# TX.net
KiCad netlist of a schematic drawn in EAGLE
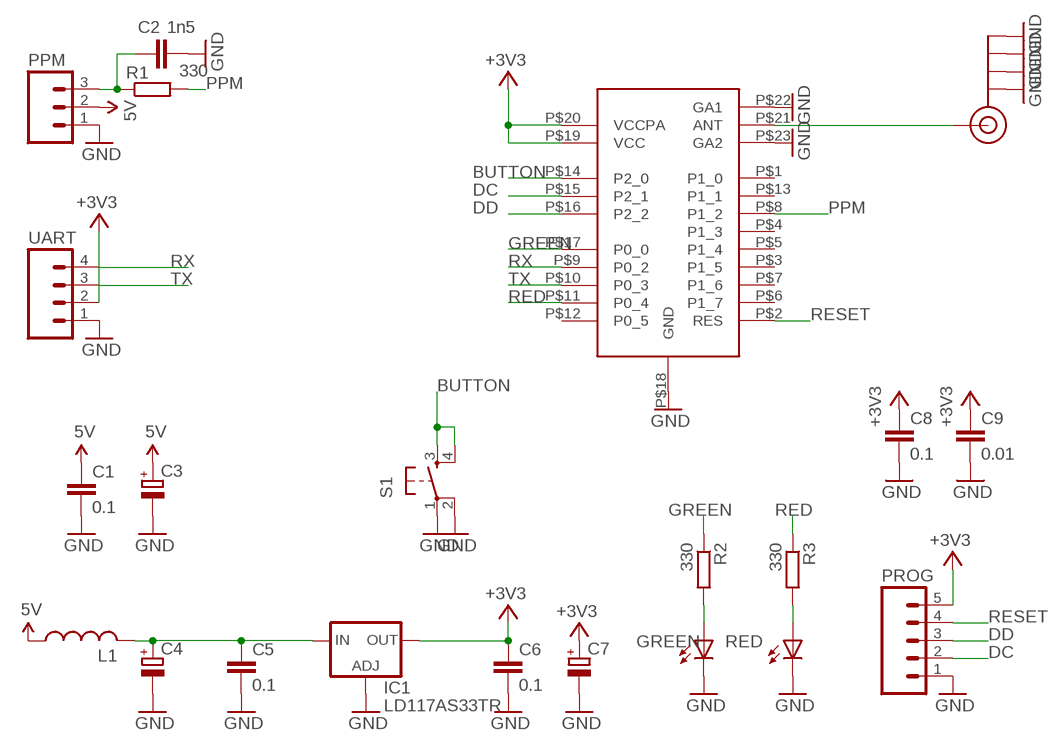
[diagram p0: schematic, sheet 1]

(export (version "E")
  (design (tool "Eeschema 10.0.6"))
  (components
    (comp (ref "C1")
      (value "0.1")
      (footprint "eagle-import:C0603")
      (libsource (lib "eagle-import") (part "C-EUC0603"))
    )
    (comp (ref "C2")
      (value "1n5")
      (footprint "eagle-import:C0603")
      (libsource (lib "eagle-import") (part "C-EUC0603"))
    )
    (comp (ref "C3")
      (value "CPOL-EUCT3216")
      (footprint "eagle-import:CT3216")
      (libsource (lib "eagle-import") (part "CPOL-EUCT3216"))
    )
    (comp (ref "C4")
      (value "CPOL-EUCT3216")
      (footprint "eagle-import:CT3216")
      (libsource (lib "eagle-import") (part "CPOL-EUCT3216"))
    )
    (comp (ref "C5")
      (value "0.1")
      (footprint "eagle-import:C0603")
      (libsource (lib "eagle-import") (part "C-EUC0603"))
    )
    (comp (ref "C6")
      (value "0.1")
      (footprint "eagle-import:C0603")
      (libsource (lib "eagle-import") (part "C-EUC0603"))
    )
    (comp (ref "C7")
      (value "CPOL-EUCT3216")
      (footprint "eagle-import:CT3216")
      (libsource (lib "eagle-import") (part "CPOL-EUCT3216"))
    )
    (comp (ref "C8")
      (value "0.1")
      (footprint "eagle-import:C0603")
      (libsource (lib "eagle-import") (part "C-EUC0603"))
    )
    (comp (ref "C9")
      (value "0.01")
      (footprint "eagle-import:C0603")
      (libsource (lib "eagle-import") (part "C-EUC0603"))
    )
    (comp (ref "GREEN")
      (value "LEDCHIPLED_1206")
      (footprint "eagle-import:CHIPLED_1206")
      (libsource (lib "eagle-import") (part "LEDCHIPLED_1206"))
    )
    (comp (ref "IC1")
      (value "LD117AS33TR")
      (footprint "eagle-import:SOT223")
      (libsource (lib "eagle-import") (part "LD117A?S33TR"))
    )
    (comp (ref "J$1")
      (value "SMA_EDGE")
      (footprint "eagle-import:SMA-EDGE")
      (libsource (lib "eagle-import") (part "SMA_EDGE"))
    )
    (comp (ref "L1")
      (value "L-USL2012C")
      (footprint "eagle-import:L2012C")
      (libsource (lib "eagle-import") (part "L-USL2012C"))
    )
    (comp (ref "PPM")
      (value "M03PTH")
      (footprint "eagle-import:1X03")
      (libsource (lib "eagle-import") (part "M03PTH"))
    )
    (comp (ref "PROG")
      (value "M05PTH")
      (footprint "eagle-import:1X05")
      (libsource (lib "eagle-import") (part "M05PTH"))
    )
    (comp (ref "R1")
      (value "330")
      (footprint "eagle-import:MINI_MELF-0102R")
      (libsource (lib "eagle-import") (part "R-EU_MELF0102R"))
    )
    (comp (ref "R2")
      (value "330")
      (footprint "eagle-import:MINI_MELF-0102R")
      (libsource (lib "eagle-import") (part "R-EU_MELF0102R"))
    )
    (comp (ref "R3")
      (value "330")
      (footprint "eagle-import:MINI_MELF-0102R")
      (libsource (lib "eagle-import") (part "R-EU_MELF0102R"))
    )
    (comp (ref "RED")
      (value "LEDCHIPLED_1206")
      (footprint "eagle-import:CHIPLED_1206")
      (libsource (lib "eagle-import") (part "LEDCHIPLED_1206"))
    )
    (comp (ref "S1")
      (value "TAC_SWITCHSMD")
      (footprint "eagle-import:TACTILE_SWITCH_SMD")
      (libsource (lib "eagle-import") (part "TAC_SWITCHSMD"))
    )
    (comp (ref "U$1")
      (value "CC1110_PA")
      (footprint "eagle-import:CC1110_PA")
      (libsource (lib "eagle-import") (part "CC1110_PA"))
    )
    (comp (ref "UART")
      (value "M04PTH")
      (footprint "eagle-import:1X04")
      (libsource (lib "eagle-import") (part "M04PTH"))
    )
  )
  (nets
    (net (code "1") (name "+3V3") (class "Default")
      (node (ref "C6") (pin "1") (pinfunction "1_1") (pintype "passive"))
      (node (ref "C7") (pin "+") (pinfunction "+_+") (pintype "passive"))
      (node (ref "C8") (pin "1") (pinfunction "1_1") (pintype "passive"))
      (node (ref "C9") (pin "1") (pinfunction "1_1") (pintype "passive"))
      (node (ref "IC1") (pin "4") (pinfunction "OUT_4") (pintype "passive"))
      (node (ref "PROG") (pin "5") (pinfunction "5_5") (pintype "passive"))
      (node (ref "U$1") (pin "P$19") (pinfunction "VCC_P$19") (pintype "bidirectional"))
      (node (ref "U$1") (pin "P$20") (pinfunction "VCCPA_P$20") (pintype "bidirectional"))
      (node (ref "UART") (pin "2") (pinfunction "2_2") (pintype "passive"))
    )
    (net (code "2") (name "/BUTTON") (class "Default")
      (node (ref "S1") (pin "3") (pinfunction "3_3") (pintype "passive"))
      (node (ref "S1") (pin "4") (pinfunction "4_4") (pintype "passive"))
      (node (ref "U$1") (pin "P$14") (pinfunction "P2_0_P$14") (pintype "bidirectional"))
    )
    (net (code "3") (name "/DC") (class "Default")
      (node (ref "PROG") (pin "2") (pinfunction "2_2") (pintype "passive"))
      (node (ref "U$1") (pin "P$15") (pinfunction "P2_1_P$15") (pintype "bidirectional"))
    )
    (net (code "4") (name "/DD") (class "Default")
      (node (ref "PROG") (pin "3") (pinfunction "3_3") (pintype "passive"))
      (node (ref "U$1") (pin "P$16") (pinfunction "P2_2_P$16") (pintype "bidirectional"))
    )
    (net (code "5") (name "/GREEN") (class "Default")
      (node (ref "R2") (pin "1") (pinfunction "1_1") (pintype "passive"))
      (node (ref "U$1") (pin "P$17") (pinfunction "P0_0_P$17") (pintype "bidirectional"))
    )
    (net (code "6") (name "/PPM") (class "Default")
      (node (ref "R1") (pin "2") (pinfunction "2_2") (pintype "passive"))
      (node (ref "U$1") (pin "P$8") (pinfunction "P1_2_P$8") (pintype "bidirectional"))
    )
    (net (code "7") (name "/RED") (class "Default")
      (node (ref "R3") (pin "1") (pinfunction "1_1") (pintype "passive"))
      (node (ref "U$1") (pin "P$11") (pinfunction "P0_4_P$11") (pintype "bidirectional"))
    )
    (net (code "8") (name "/RESET") (class "Default")
      (node (ref "PROG") (pin "4") (pinfunction "4_4") (pintype "passive"))
      (node (ref "U$1") (pin "P$2") (pinfunction "RES_P$2") (pintype "bidirectional"))
    )
    (net (code "9") (name "/RX") (class "Default")
      (node (ref "U$1") (pin "P$9") (pinfunction "P0_2_P$9") (pintype "bidirectional"))
      (node (ref "UART") (pin "4") (pinfunction "4_4") (pintype "passive"))
    )
    (net (code "10") (name "/TX") (class "Default")
      (node (ref "U$1") (pin "P$10") (pinfunction "P0_3_P$10") (pintype "bidirectional"))
      (node (ref "UART") (pin "3") (pinfunction "3_3") (pintype "passive"))
    )
    (net (code "11") (name "5V") (class "Default")
      (node (ref "C1") (pin "1") (pinfunction "1_1") (pintype "passive"))
      (node (ref "C3") (pin "+") (pinfunction "+_+") (pintype "passive"))
      (node (ref "L1") (pin "1") (pinfunction "1_1") (pintype "passive"))
      (node (ref "PPM") (pin "2") (pinfunction "2_2") (pintype "passive"))
    )
    (net (code "12") (name "GND") (class "Default")
      (node (ref "C1") (pin "2") (pinfunction "2_2") (pintype "passive"))
      (node (ref "C2") (pin "2") (pinfunction "2_2") (pintype "passive"))
      (node (ref "C3") (pin "-") (pinfunction "-_-") (pintype "passive"))
      (node (ref "C4") (pin "-") (pinfunction "-_-") (pintype "passive"))
      (node (ref "C5") (pin "2") (pinfunction "2_2") (pintype "passive"))
      (node (ref "C6") (pin "2") (pinfunction "2_2") (pintype "passive"))
      (node (ref "C7") (pin "-") (pinfunction "-_-") (pintype "passive"))
      (node (ref "C8") (pin "2") (pinfunction "2_2") (pintype "passive"))
      (node (ref "C9") (pin "2") (pinfunction "2_2") (pintype "passive"))
      (node (ref "GREEN") (pin "C") (pinfunction "C_C") (pintype "passive"))
      (node (ref "IC1") (pin "1") (pinfunction "ADJ_1") (pintype "input"))
      (node (ref "J$1") (pin "GND@0") (pinfunction "GND_GND@0") (pintype "bidirectional"))
      (node (ref "J$1") (pin "GND@1") (pinfunction "GND_GND@1") (pintype "bidirectional"))
      (node (ref "J$1") (pin "GND@2") (pinfunction "GND_GND@2") (pintype "bidirectional"))
      (node (ref "J$1") (pin "GND@3") (pinfunction "GND_GND@3") (pintype "bidirectional"))
      (node (ref "PPM") (pin "1") (pinfunction "1_1") (pintype "passive"))
      (node (ref "PROG") (pin "1") (pinfunction "1_1") (pintype "passive"))
      (node (ref "RED") (pin "C") (pinfunction "C_C") (pintype "passive"))
      (node (ref "S1") (pin "1") (pinfunction "1_1") (pintype "passive"))
      (node (ref "S1") (pin "2") (pinfunction "2_2") (pintype "passive"))
      (node (ref "U$1") (pin "P$18") (pinfunction "GND_P$18") (pintype "bidirectional"))
      (node (ref "U$1") (pin "P$22") (pinfunction "GA1_P$22") (pintype "bidirectional"))
      (node (ref "U$1") (pin "P$23") (pinfunction "GA2_P$23") (pintype "bidirectional"))
      (node (ref "UART") (pin "1") (pinfunction "1_1") (pintype "passive"))
    )
    (net (code "13") (name "Net-(C2-Pad1)") (class "Default")
      (node (ref "C2") (pin "1") (pinfunction "1_1") (pintype "passive"))
      (node (ref "PPM") (pin "3") (pinfunction "3_3") (pintype "passive"))
      (node (ref "R1") (pin "1") (pinfunction "1_1") (pintype "passive"))
    )
    (net (code "14") (name "Net-(GREEN-PadA)") (class "Default")
      (node (ref "GREEN") (pin "A") (pinfunction "A_A") (pintype "passive"))
      (node (ref "R2") (pin "2") (pinfunction "2_2") (pintype "passive"))
    )
    (net (code "15") (name "Net-(IC1-IN)") (class "Default")
      (node (ref "C4") (pin "+") (pinfunction "+_+") (pintype "passive"))
      (node (ref "C5") (pin "1") (pinfunction "1_1") (pintype "passive"))
      (node (ref "IC1") (pin "3") (pinfunction "IN_3") (pintype "input"))
      (node (ref "L1") (pin "2") (pinfunction "2_2") (pintype "passive"))
    )
    (net (code "16") (name "Net-(J$1-SIGNAL)") (class "Default")
      (node (ref "J$1") (pin "SIG") (pinfunction "SIGNAL_SIG") (pintype "bidirectional"))
      (node (ref "U$1") (pin "P$21") (pinfunction "ANT_P$21") (pintype "bidirectional"))
    )
    (net (code "17") (name "Net-(R3-Pad2)") (class "Default")
      (node (ref "R3") (pin "2") (pinfunction "2_2") (pintype "passive"))
      (node (ref "RED") (pin "A") (pinfunction "A_A") (pintype "passive"))
    )
    (net (code "18") (name "unconnected-(U$1-P0_5-PadP$12)") (class "Default")
      (node (ref "U$1") (pin "P$12") (pinfunction "P0_5_P$12") (pintype "bidirectional"))
    )
    (net (code "19") (name "unconnected-(U$1-P1_0-PadP$1)") (class "Default")
      (node (ref "U$1") (pin "P$1") (pinfunction "P1_0_P$1") (pintype "bidirectional"))
    )
    (net (code "20") (name "unconnected-(U$1-P1_1-PadP$13)") (class "Default")
      (node (ref "U$1") (pin "P$13") (pinfunction "P1_1_P$13") (pintype "bidirectional"))
    )
    (net (code "21") (name "unconnected-(U$1-P1_3-PadP$4)") (class "Default")
      (node (ref "U$1") (pin "P$4") (pinfunction "P1_3_P$4") (pintype "bidirectional"))
    )
    (net (code "22") (name "unconnected-(U$1-P1_4-PadP$5)") (class "Default")
      (node (ref "U$1") (pin "P$5") (pinfunction "P1_4_P$5") (pintype "bidirectional"))
    )
    (net (code "23") (name "unconnected-(U$1-P1_5-PadP$3)") (class "Default")
      (node (ref "U$1") (pin "P$3") (pinfunction "P1_5_P$3") (pintype "bidirectional"))
    )
    (net (code "24") (name "unconnected-(U$1-P1_6-PadP$7)") (class "Default")
      (node (ref "U$1") (pin "P$7") (pinfunction "P1_6_P$7") (pintype "bidirectional"))
    )
    (net (code "25") (name "unconnected-(U$1-P1_7-PadP$6)") (class "Default")
      (node (ref "U$1") (pin "P$6") (pinfunction "P1_7_P$6") (pintype "bidirectional"))
    )
  )
)
